# P_IN.net
KiCad netlist of a schematic drawn in Altium Designer
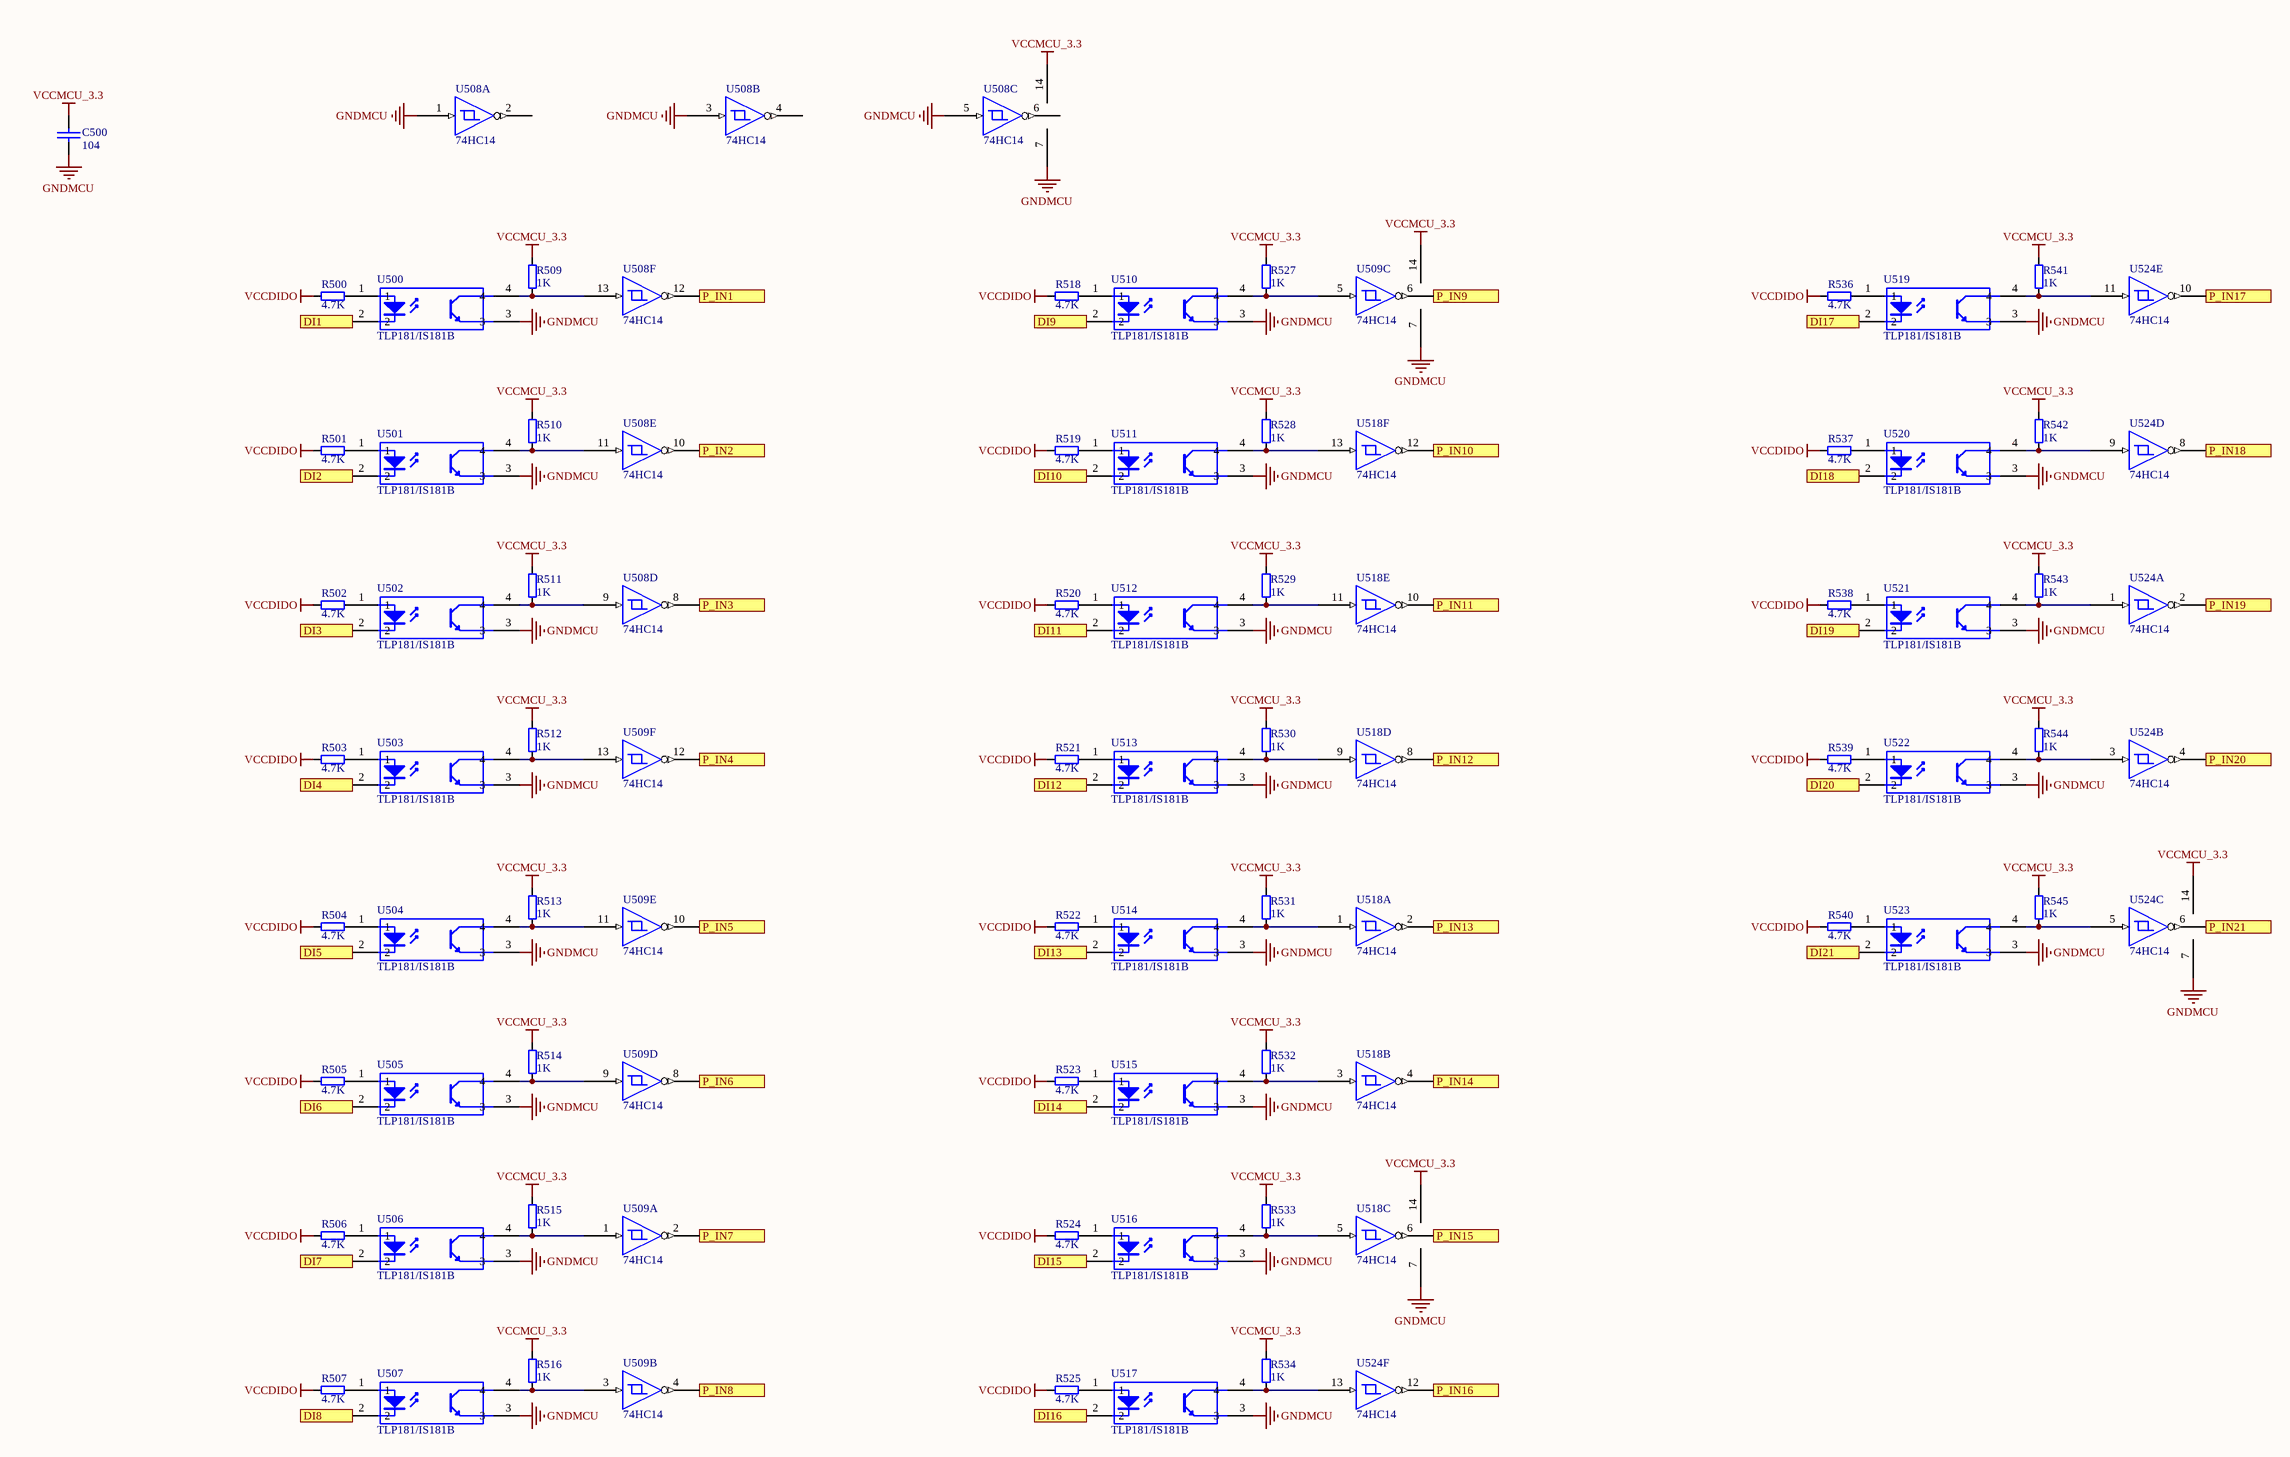
[diagram p0: P_IN.SchDoc]

(export (version "E")
  (design (tool "Eeschema 10.0.6"))
  (components
    (comp (ref "C500")
      (value "104")
      (footprint "CAPC_E0805_2012X70N")
      (description "Capacitor")
      (libsource (lib "YGInfoSCHLib") (part "CAP"))
    )
    (comp (ref "R500")
      (value "4.7K")
      (footprint "RESC_E0805_2012X50N")
      (description "General Resistor")
      (libsource (lib "Resistor") (part "Res"))
    )
    (comp (ref "R501")
      (value "4.7K")
      (footprint "RESC_E0805_2012X50N")
      (description "General Resistor")
      (libsource (lib "Resistor") (part "Res"))
    )
    (comp (ref "R502")
      (value "4.7K")
      (footprint "RESC_E0805_2012X50N")
      (description "General Resistor")
      (libsource (lib "Resistor") (part "Res"))
    )
    (comp (ref "R503")
      (value "4.7K")
      (footprint "RESC_E0805_2012X50N")
      (description "General Resistor")
      (libsource (lib "Resistor") (part "Res"))
    )
    (comp (ref "R504")
      (value "4.7K")
      (footprint "RESC_E0805_2012X50N")
      (description "General Resistor")
      (libsource (lib "Resistor") (part "Res"))
    )
    (comp (ref "R505")
      (value "4.7K")
      (footprint "RESC_E0805_2012X50N")
      (description "General Resistor")
      (libsource (lib "Resistor") (part "Res"))
    )
    (comp (ref "R506")
      (value "4.7K")
      (footprint "RESC_E0805_2012X50N")
      (description "General Resistor")
      (libsource (lib "Resistor") (part "Res"))
    )
    (comp (ref "R507")
      (value "4.7K")
      (footprint "RESC_E0805_2012X50N")
      (description "General Resistor")
      (libsource (lib "Resistor") (part "Res"))
    )
    (comp (ref "R509")
      (value "1K")
      (footprint "RESC_E0805_2012X50N")
      (description "General Resistor")
      (libsource (lib "") (part "Res_1"))
    )
    (comp (ref "R510")
      (value "1K")
      (footprint "RESC_E0805_2012X50N")
      (description "General Resistor")
      (libsource (lib "") (part "Res_1"))
    )
    (comp (ref "R511")
      (value "1K")
      (footprint "RESC_E0805_2012X50N")
      (description "General Resistor")
      (libsource (lib "") (part "Res_1"))
    )
    (comp (ref "R512")
      (value "1K")
      (footprint "RESC_E0805_2012X50N")
      (description "General Resistor")
      (libsource (lib "") (part "Res_1"))
    )
    (comp (ref "R513")
      (value "1K")
      (footprint "RESC_E0805_2012X50N")
      (description "General Resistor")
      (libsource (lib "") (part "Res_1"))
    )
    (comp (ref "R514")
      (value "1K")
      (footprint "RESC_E0805_2012X50N")
      (description "General Resistor")
      (libsource (lib "") (part "Res_1"))
    )
    (comp (ref "R515")
      (value "1K")
      (footprint "RESC_E0805_2012X50N")
      (description "General Resistor")
      (libsource (lib "") (part "Res_1"))
    )
    (comp (ref "R516")
      (value "1K")
      (footprint "RESC_E0805_2012X50N")
      (description "General Resistor")
      (libsource (lib "") (part "Res_1"))
    )
    (comp (ref "R518")
      (value "4.7K")
      (footprint "RESC_E0805_2012X50N")
      (description "General Resistor")
      (libsource (lib "Resistor") (part "Res"))
    )
    (comp (ref "R519")
      (value "4.7K")
      (footprint "RESC_E0805_2012X50N")
      (description "General Resistor")
      (libsource (lib "Resistor") (part "Res"))
    )
    (comp (ref "R520")
      (value "4.7K")
      (footprint "RESC_E0805_2012X50N")
      (description "General Resistor")
      (libsource (lib "Resistor") (part "Res"))
    )
    (comp (ref "R521")
      (value "4.7K")
      (footprint "RESC_E0805_2012X50N")
      (description "General Resistor")
      (libsource (lib "Resistor") (part "Res"))
    )
    (comp (ref "R522")
      (value "4.7K")
      (footprint "RESC_E0805_2012X50N")
      (description "General Resistor")
      (libsource (lib "Resistor") (part "Res"))
    )
    (comp (ref "R523")
      (value "4.7K")
      (footprint "RESC_E0805_2012X50N")
      (description "General Resistor")
      (libsource (lib "Resistor") (part "Res"))
    )
    (comp (ref "R524")
      (value "4.7K")
      (footprint "RESC_E0805_2012X50N")
      (description "General Resistor")
      (libsource (lib "Resistor") (part "Res"))
    )
    (comp (ref "R525")
      (value "4.7K")
      (footprint "RESC_E0805_2012X50N")
      (description "General Resistor")
      (libsource (lib "Resistor") (part "Res"))
    )
    (comp (ref "R527")
      (value "1K")
      (footprint "RESC_E0805_2012X50N")
      (description "General Resistor")
      (libsource (lib "") (part "Res_1"))
    )
    (comp (ref "R528")
      (value "1K")
      (footprint "RESC_E0805_2012X50N")
      (description "General Resistor")
      (libsource (lib "") (part "Res_1"))
    )
    (comp (ref "R529")
      (value "1K")
      (footprint "RESC_E0805_2012X50N")
      (description "General Resistor")
      (libsource (lib "") (part "Res_1"))
    )
    (comp (ref "R530")
      (value "1K")
      (footprint "RESC_E0805_2012X50N")
      (description "General Resistor")
      (libsource (lib "") (part "Res_1"))
    )
    (comp (ref "R531")
      (value "1K")
      (footprint "RESC_E0805_2012X50N")
      (description "General Resistor")
      (libsource (lib "") (part "Res_1"))
    )
    (comp (ref "R532")
      (value "1K")
      (footprint "RESC_E0805_2012X50N")
      (description "General Resistor")
      (libsource (lib "") (part "Res_1"))
    )
    (comp (ref "R533")
      (value "1K")
      (footprint "RESC_E0805_2012X50N")
      (description "General Resistor")
      (libsource (lib "") (part "Res_1"))
    )
    (comp (ref "R534")
      (value "1K")
      (footprint "RESC_E0805_2012X50N")
      (description "General Resistor")
      (libsource (lib "") (part "Res_1"))
    )
    (comp (ref "R536")
      (value "4.7K")
      (footprint "RESC_E0805_2012X50N")
      (description "General Resistor")
      (libsource (lib "Resistor") (part "Res"))
    )
    (comp (ref "R537")
      (value "4.7K")
      (footprint "RESC_E0805_2012X50N")
      (description "General Resistor")
      (libsource (lib "Resistor") (part "Res"))
    )
    (comp (ref "R538")
      (value "4.7K")
      (footprint "RESC_E0805_2012X50N")
      (description "General Resistor")
      (libsource (lib "Resistor") (part "Res"))
    )
    (comp (ref "R539")
      (value "4.7K")
      (footprint "RESC_E0805_2012X50N")
      (description "General Resistor")
      (libsource (lib "Resistor") (part "Res"))
    )
    (comp (ref "R540")
      (value "4.7K")
      (footprint "RESC_E0805_2012X50N")
      (description "General Resistor")
      (libsource (lib "Resistor") (part "Res"))
    )
    (comp (ref "R541")
      (value "1K")
      (footprint "RESC_E0805_2012X50N")
      (description "General Resistor")
      (libsource (lib "") (part "Res_1"))
    )
    (comp (ref "R542")
      (value "1K")
      (footprint "RESC_E0805_2012X50N")
      (description "General Resistor")
      (libsource (lib "") (part "Res_1"))
    )
    (comp (ref "R543")
      (value "1K")
      (footprint "RESC_E0805_2012X50N")
      (description "General Resistor")
      (libsource (lib "") (part "Res_1"))
    )
    (comp (ref "R544")
      (value "1K")
      (footprint "RESC_E0805_2012X50N")
      (description "General Resistor")
      (libsource (lib "") (part "Res_1"))
    )
    (comp (ref "R545")
      (value "1K")
      (footprint "RESC_E0805_2012X50N")
      (description "General Resistor")
      (libsource (lib "") (part "Res_1"))
    )
    (comp (ref "U500")
      (value "TLP181/IS181B")
      (footprint "TLP181")
      (description "光耦隔离")
      (libsource (lib "YGInfoSCHLib") (part "TLP181"))
    )
    (comp (ref "U501")
      (value "TLP181/IS181B")
      (footprint "TLP181")
      (description "光耦隔离")
      (libsource (lib "YGInfoSCHLib") (part "TLP181"))
    )
    (comp (ref "U502")
      (value "TLP181/IS181B")
      (footprint "TLP181")
      (description "光耦隔离")
      (libsource (lib "YGInfoSCHLib") (part "TLP181"))
    )
    (comp (ref "U503")
      (value "TLP181/IS181B")
      (footprint "TLP181")
      (description "光耦隔离")
      (libsource (lib "YGInfoSCHLib") (part "TLP181"))
    )
    (comp (ref "U504")
      (value "TLP181/IS181B")
      (footprint "TLP181")
      (description "光耦隔离")
      (libsource (lib "YGInfoSCHLib") (part "TLP181"))
    )
    (comp (ref "U505")
      (value "TLP181/IS181B")
      (footprint "TLP181")
      (description "光耦隔离")
      (libsource (lib "YGInfoSCHLib") (part "TLP181"))
    )
    (comp (ref "U506")
      (value "TLP181/IS181B")
      (footprint "TLP181")
      (description "光耦隔离")
      (libsource (lib "YGInfoSCHLib") (part "TLP181"))
    )
    (comp (ref "U507")
      (value "TLP181/IS181B")
      (footprint "TLP181")
      (description "光耦隔离")
      (libsource (lib "YGInfoSCHLib") (part "TLP181"))
    )
    (comp (ref "U508") (value "74HC14") (footprint "SO-14") (libsource (lib "YGInfoSCHLib") (part "74LS14")))
    (comp (ref "U509") (value "74HC14") (footprint "SO-14") (libsource (lib "YGInfoSCHLib") (part "74LS14")))
    (comp (ref "U510")
      (value "TLP181/IS181B")
      (footprint "TLP181")
      (description "光耦隔离")
      (libsource (lib "YGInfoSCHLib") (part "TLP181"))
    )
    (comp (ref "U511")
      (value "TLP181/IS181B")
      (footprint "TLP181")
      (description "光耦隔离")
      (libsource (lib "YGInfoSCHLib") (part "TLP181"))
    )
    (comp (ref "U512")
      (value "TLP181/IS181B")
      (footprint "TLP181")
      (description "光耦隔离")
      (libsource (lib "YGInfoSCHLib") (part "TLP181"))
    )
    (comp (ref "U513")
      (value "TLP181/IS181B")
      (footprint "TLP181")
      (description "光耦隔离")
      (libsource (lib "YGInfoSCHLib") (part "TLP181"))
    )
    (comp (ref "U514")
      (value "TLP181/IS181B")
      (footprint "TLP181")
      (description "光耦隔离")
      (libsource (lib "YGInfoSCHLib") (part "TLP181"))
    )
    (comp (ref "U515")
      (value "TLP181/IS181B")
      (footprint "TLP181")
      (description "光耦隔离")
      (libsource (lib "YGInfoSCHLib") (part "TLP181"))
    )
    (comp (ref "U516")
      (value "TLP181/IS181B")
      (footprint "TLP181")
      (description "光耦隔离")
      (libsource (lib "YGInfoSCHLib") (part "TLP181"))
    )
    (comp (ref "U517")
      (value "TLP181/IS181B")
      (footprint "TLP181")
      (description "光耦隔离")
      (libsource (lib "YGInfoSCHLib") (part "TLP181"))
    )
    (comp (ref "U518") (value "74HC14") (footprint "SO-14") (libsource (lib "") (part "74LS14_5")))
    (comp (ref "U519")
      (value "TLP181/IS181B")
      (footprint "TLP181")
      (description "光耦隔离")
      (libsource (lib "YGInfoSCHLib") (part "TLP181"))
    )
    (comp (ref "U520")
      (value "TLP181/IS181B")
      (footprint "TLP181")
      (description "光耦隔离")
      (libsource (lib "YGInfoSCHLib") (part "TLP181"))
    )
    (comp (ref "U521")
      (value "TLP181/IS181B")
      (footprint "TLP181")
      (description "光耦隔离")
      (libsource (lib "YGInfoSCHLib") (part "TLP181"))
    )
    (comp (ref "U522")
      (value "TLP181/IS181B")
      (footprint "TLP181")
      (description "光耦隔离")
      (libsource (lib "YGInfoSCHLib") (part "TLP181"))
    )
    (comp (ref "U523")
      (value "TLP181/IS181B")
      (footprint "TLP181")
      (description "光耦隔离")
      (libsource (lib "YGInfoSCHLib") (part "TLP181"))
    )
    (comp (ref "U524") (value "74HC14") (footprint "SO-14") (libsource (lib "") (part "74LS14_4")))
  )
  (nets
    (net (code "1") (name "/DI1") (class "Default")
      (node (ref "U500") (pin "2") (pinfunction "2_2") (pintype "passive"))
    )
    (net (code "2") (name "/DI2") (class "Default")
      (node (ref "U501") (pin "2") (pinfunction "2_2") (pintype "passive"))
    )
    (net (code "3") (name "/DI3") (class "Default")
      (node (ref "U502") (pin "2") (pinfunction "2_2") (pintype "passive"))
    )
    (net (code "4") (name "/DI4") (class "Default")
      (node (ref "U503") (pin "2") (pinfunction "2_2") (pintype "passive"))
    )
    (net (code "5") (name "/DI5") (class "Default")
      (node (ref "U504") (pin "2") (pinfunction "2_2") (pintype "passive"))
    )
    (net (code "6") (name "/DI6") (class "Default")
      (node (ref "U505") (pin "2") (pinfunction "2_2") (pintype "passive"))
    )
    (net (code "7") (name "/DI7") (class "Default")
      (node (ref "U506") (pin "2") (pinfunction "2_2") (pintype "passive"))
    )
    (net (code "8") (name "/DI8") (class "Default")
      (node (ref "U507") (pin "2") (pinfunction "2_2") (pintype "passive"))
    )
    (net (code "9") (name "/DI9") (class "Default")
      (node (ref "U510") (pin "2") (pinfunction "2_2") (pintype "passive"))
    )
    (net (code "10") (name "/DI10") (class "Default")
      (node (ref "U511") (pin "2") (pinfunction "2_2") (pintype "passive"))
    )
    (net (code "11") (name "/DI11") (class "Default")
      (node (ref "U512") (pin "2") (pinfunction "2_2") (pintype "passive"))
    )
    (net (code "12") (name "/DI12") (class "Default")
      (node (ref "U513") (pin "2") (pinfunction "2_2") (pintype "passive"))
    )
    (net (code "13") (name "/DI13") (class "Default")
      (node (ref "U514") (pin "2") (pinfunction "2_2") (pintype "passive"))
    )
    (net (code "14") (name "/DI14") (class "Default")
      (node (ref "U515") (pin "2") (pinfunction "2_2") (pintype "passive"))
    )
    (net (code "15") (name "/DI15") (class "Default")
      (node (ref "U516") (pin "2") (pinfunction "2_2") (pintype "passive"))
    )
    (net (code "16") (name "/DI16") (class "Default")
      (node (ref "U517") (pin "2") (pinfunction "2_2") (pintype "passive"))
    )
    (net (code "17") (name "/DI17") (class "Default")
      (node (ref "U519") (pin "2") (pinfunction "2_2") (pintype "passive"))
    )
    (net (code "18") (name "/DI18") (class "Default")
      (node (ref "U520") (pin "2") (pinfunction "2_2") (pintype "passive"))
    )
    (net (code "19") (name "/DI19") (class "Default")
      (node (ref "U521") (pin "2") (pinfunction "2_2") (pintype "passive"))
    )
    (net (code "20") (name "/DI20") (class "Default")
      (node (ref "U522") (pin "2") (pinfunction "2_2") (pintype "passive"))
    )
    (net (code "21") (name "/DI21") (class "Default")
      (node (ref "U523") (pin "2") (pinfunction "2_2") (pintype "passive"))
    )
    (net (code "22") (name "/P_IN1") (class "Default") (node (ref "U508") (pin "12") (pintype "output")))
    (net (code "23") (name "/P_IN2") (class "Default") (node (ref "U508") (pin "10") (pintype "output")))
    (net (code "24") (name "/P_IN3") (class "Default") (node (ref "U508") (pin "8") (pintype "output")))
    (net (code "25") (name "/P_IN4") (class "Default") (node (ref "U509") (pin "12") (pintype "output")))
    (net (code "26") (name "/P_IN5") (class "Default") (node (ref "U509") (pin "10") (pintype "output")))
    (net (code "27") (name "/P_IN6") (class "Default") (node (ref "U509") (pin "8") (pintype "output")))
    (net (code "28") (name "/P_IN7") (class "Default") (node (ref "U509") (pin "2") (pintype "output")))
    (net (code "29") (name "/P_IN8") (class "Default") (node (ref "U509") (pin "4") (pintype "output")))
    (net (code "30") (name "/P_IN9") (class "Default") (node (ref "U509") (pin "6") (pintype "output")))
    (net (code "31") (name "/P_IN10") (class "Default") (node (ref "U518") (pin "12") (pintype "output")))
    (net (code "32") (name "/P_IN11") (class "Default") (node (ref "U518") (pin "10") (pintype "output")))
    (net (code "33") (name "/P_IN12") (class "Default") (node (ref "U518") (pin "8") (pintype "output")))
    (net (code "34") (name "/P_IN13") (class "Default") (node (ref "U518") (pin "2") (pintype "output")))
    (net (code "35") (name "/P_IN14") (class "Default") (node (ref "U518") (pin "4") (pintype "output")))
    (net (code "36") (name "/P_IN15") (class "Default") (node (ref "U518") (pin "6") (pintype "output")))
    (net (code "37") (name "/P_IN16") (class "Default") (node (ref "U524") (pin "12") (pintype "output")))
    (net (code "38") (name "/P_IN17") (class "Default") (node (ref "U524") (pin "10") (pintype "output")))
    (net (code "39") (name "/P_IN18") (class "Default") (node (ref "U524") (pin "8") (pintype "output")))
    (net (code "40") (name "/P_IN19") (class "Default") (node (ref "U524") (pin "2") (pintype "output")))
    (net (code "41") (name "/P_IN20") (class "Default") (node (ref "U524") (pin "4") (pintype "output")))
    (net (code "42") (name "/P_IN21") (class "Default") (node (ref "U524") (pin "6") (pintype "output")))
    (net (code "43") (name "GNDMCU") (class "Default")
      (node (ref "C500") (pin "2") (pinfunction "2_2") (pintype "passive"))
      (node (ref "U500") (pin "3") (pinfunction "3_3") (pintype "passive"))
      (node (ref "U501") (pin "3") (pinfunction "3_3") (pintype "passive"))
      (node (ref "U502") (pin "3") (pinfunction "3_3") (pintype "passive"))
      (node (ref "U503") (pin "3") (pinfunction "3_3") (pintype "passive"))
      (node (ref "U504") (pin "3") (pinfunction "3_3") (pintype "passive"))
      (node (ref "U505") (pin "3") (pinfunction "3_3") (pintype "passive"))
      (node (ref "U506") (pin "3") (pinfunction "3_3") (pintype "passive"))
      (node (ref "U507") (pin "3") (pinfunction "3_3") (pintype "passive"))
      (node (ref "U508") (pin "1") (pintype "input"))
      (node (ref "U508") (pin "3") (pintype "input"))
      (node (ref "U508") (pin "5") (pintype "input"))
      (node (ref "U508") (pin "7") (pintype "power_in"))
      (node (ref "U509") (pin "7") (pintype "power_in"))
      (node (ref "U510") (pin "3") (pinfunction "3_3") (pintype "passive"))
      (node (ref "U511") (pin "3") (pinfunction "3_3") (pintype "passive"))
      (node (ref "U512") (pin "3") (pinfunction "3_3") (pintype "passive"))
      (node (ref "U513") (pin "3") (pinfunction "3_3") (pintype "passive"))
      (node (ref "U514") (pin "3") (pinfunction "3_3") (pintype "passive"))
      (node (ref "U515") (pin "3") (pinfunction "3_3") (pintype "passive"))
      (node (ref "U516") (pin "3") (pinfunction "3_3") (pintype "passive"))
      (node (ref "U517") (pin "3") (pinfunction "3_3") (pintype "passive"))
      (node (ref "U518") (pin "7") (pintype "power_in"))
      (node (ref "U519") (pin "3") (pinfunction "3_3") (pintype "passive"))
      (node (ref "U520") (pin "3") (pinfunction "3_3") (pintype "passive"))
      (node (ref "U521") (pin "3") (pinfunction "3_3") (pintype "passive"))
      (node (ref "U522") (pin "3") (pinfunction "3_3") (pintype "passive"))
      (node (ref "U523") (pin "3") (pinfunction "3_3") (pintype "passive"))
      (node (ref "U524") (pin "7") (pintype "power_in"))
    )
    (net (code "44") (name "Net-(R500-Pad1)") (class "Default")
      (node (ref "R500") (pin "1") (pinfunction "1_1") (pintype "passive"))
      (node (ref "U500") (pin "1") (pinfunction "1_1") (pintype "passive"))
    )
    (net (code "45") (name "Net-(R501-Pad1)") (class "Default")
      (node (ref "R501") (pin "1") (pinfunction "1_1") (pintype "passive"))
      (node (ref "U501") (pin "1") (pinfunction "1_1") (pintype "passive"))
    )
    (net (code "46") (name "Net-(R502-Pad1)") (class "Default")
      (node (ref "R502") (pin "1") (pinfunction "1_1") (pintype "passive"))
      (node (ref "U502") (pin "1") (pinfunction "1_1") (pintype "passive"))
    )
    (net (code "47") (name "Net-(R503-Pad1)") (class "Default")
      (node (ref "R503") (pin "1") (pinfunction "1_1") (pintype "passive"))
      (node (ref "U503") (pin "1") (pinfunction "1_1") (pintype "passive"))
    )
    (net (code "48") (name "Net-(R504-Pad1)") (class "Default")
      (node (ref "R504") (pin "1") (pinfunction "1_1") (pintype "passive"))
      (node (ref "U504") (pin "1") (pinfunction "1_1") (pintype "passive"))
    )
    (net (code "49") (name "Net-(R505-Pad1)") (class "Default")
      (node (ref "R505") (pin "1") (pinfunction "1_1") (pintype "passive"))
      (node (ref "U505") (pin "1") (pinfunction "1_1") (pintype "passive"))
    )
    (net (code "50") (name "Net-(R506-Pad1)") (class "Default")
      (node (ref "R506") (pin "1") (pinfunction "1_1") (pintype "passive"))
      (node (ref "U506") (pin "1") (pinfunction "1_1") (pintype "passive"))
    )
    (net (code "51") (name "Net-(R507-Pad1)") (class "Default")
      (node (ref "R507") (pin "1") (pinfunction "1_1") (pintype "passive"))
      (node (ref "U507") (pin "1") (pinfunction "1_1") (pintype "passive"))
    )
    (net (code "52") (name "Net-(R509-Pad1)") (class "Default")
      (node (ref "R509") (pin "1") (pinfunction "1_1") (pintype "passive"))
      (node (ref "U500") (pin "4") (pinfunction "4_4") (pintype "passive"))
      (node (ref "U508") (pin "13") (pintype "input"))
    )
    (net (code "53") (name "Net-(R510-Pad1)") (class "Default")
      (node (ref "R510") (pin "1") (pinfunction "1_1") (pintype "passive"))
      (node (ref "U501") (pin "4") (pinfunction "4_4") (pintype "passive"))
      (node (ref "U508") (pin "11") (pintype "input"))
    )
    (net (code "54") (name "Net-(R511-Pad1)") (class "Default")
      (node (ref "R511") (pin "1") (pinfunction "1_1") (pintype "passive"))
      (node (ref "U502") (pin "4") (pinfunction "4_4") (pintype "passive"))
      (node (ref "U508") (pin "9") (pintype "input"))
    )
    (net (code "55") (name "Net-(R512-Pad1)") (class "Default")
      (node (ref "R512") (pin "1") (pinfunction "1_1") (pintype "passive"))
      (node (ref "U503") (pin "4") (pinfunction "4_4") (pintype "passive"))
      (node (ref "U509") (pin "13") (pintype "input"))
    )
    (net (code "56") (name "Net-(R513-Pad1)") (class "Default")
      (node (ref "R513") (pin "1") (pinfunction "1_1") (pintype "passive"))
      (node (ref "U504") (pin "4") (pinfunction "4_4") (pintype "passive"))
      (node (ref "U509") (pin "11") (pintype "input"))
    )
    (net (code "57") (name "Net-(R514-Pad1)") (class "Default")
      (node (ref "R514") (pin "1") (pinfunction "1_1") (pintype "passive"))
      (node (ref "U505") (pin "4") (pinfunction "4_4") (pintype "passive"))
      (node (ref "U509") (pin "9") (pintype "input"))
    )
    (net (code "58") (name "Net-(R515-Pad1)") (class "Default")
      (node (ref "R515") (pin "1") (pinfunction "1_1") (pintype "passive"))
      (node (ref "U506") (pin "4") (pinfunction "4_4") (pintype "passive"))
      (node (ref "U509") (pin "1") (pintype "input"))
    )
    (net (code "59") (name "Net-(R516-Pad1)") (class "Default")
      (node (ref "R516") (pin "1") (pinfunction "1_1") (pintype "passive"))
      (node (ref "U507") (pin "4") (pinfunction "4_4") (pintype "passive"))
      (node (ref "U509") (pin "3") (pintype "input"))
    )
    (net (code "60") (name "Net-(R518-Pad1)") (class "Default")
      (node (ref "R518") (pin "1") (pinfunction "1_1") (pintype "passive"))
      (node (ref "U510") (pin "1") (pinfunction "1_1") (pintype "passive"))
    )
    (net (code "61") (name "Net-(R519-Pad1)") (class "Default")
      (node (ref "R519") (pin "1") (pinfunction "1_1") (pintype "passive"))
      (node (ref "U511") (pin "1") (pinfunction "1_1") (pintype "passive"))
    )
    (net (code "62") (name "Net-(R520-Pad1)") (class "Default")
      (node (ref "R520") (pin "1") (pinfunction "1_1") (pintype "passive"))
      (node (ref "U512") (pin "1") (pinfunction "1_1") (pintype "passive"))
    )
    (net (code "63") (name "Net-(R521-Pad1)") (class "Default")
      (node (ref "R521") (pin "1") (pinfunction "1_1") (pintype "passive"))
      (node (ref "U513") (pin "1") (pinfunction "1_1") (pintype "passive"))
    )
    (net (code "64") (name "Net-(R522-Pad1)") (class "Default")
      (node (ref "R522") (pin "1") (pinfunction "1_1") (pintype "passive"))
      (node (ref "U514") (pin "1") (pinfunction "1_1") (pintype "passive"))
    )
    (net (code "65") (name "Net-(R523-Pad1)") (class "Default")
      (node (ref "R523") (pin "1") (pinfunction "1_1") (pintype "passive"))
      (node (ref "U515") (pin "1") (pinfunction "1_1") (pintype "passive"))
    )
    (net (code "66") (name "Net-(R524-Pad1)") (class "Default")
      (node (ref "R524") (pin "1") (pinfunction "1_1") (pintype "passive"))
      (node (ref "U516") (pin "1") (pinfunction "1_1") (pintype "passive"))
    )
    (net (code "67") (name "Net-(R525-Pad1)") (class "Default")
      (node (ref "R525") (pin "1") (pinfunction "1_1") (pintype "passive"))
      (node (ref "U517") (pin "1") (pinfunction "1_1") (pintype "passive"))
    )
    (net (code "68") (name "Net-(R527-Pad1)") (class "Default")
      (node (ref "R527") (pin "1") (pinfunction "1_1") (pintype "passive"))
      (node (ref "U509") (pin "5") (pintype "input"))
      (node (ref "U510") (pin "4") (pinfunction "4_4") (pintype "passive"))
    )
    (net (code "69") (name "Net-(R528-Pad1)") (class "Default")
      (node (ref "R528") (pin "1") (pinfunction "1_1") (pintype "passive"))
      (node (ref "U511") (pin "4") (pinfunction "4_4") (pintype "passive"))
      (node (ref "U518") (pin "13") (pintype "input"))
    )
    (net (code "70") (name "Net-(R529-Pad1)") (class "Default")
      (node (ref "R529") (pin "1") (pinfunction "1_1") (pintype "passive"))
      (node (ref "U512") (pin "4") (pinfunction "4_4") (pintype "passive"))
      (node (ref "U518") (pin "11") (pintype "input"))
    )
    (net (code "71") (name "Net-(R530-Pad1)") (class "Default")
      (node (ref "R530") (pin "1") (pinfunction "1_1") (pintype "passive"))
      (node (ref "U513") (pin "4") (pinfunction "4_4") (pintype "passive"))
      (node (ref "U518") (pin "9") (pintype "input"))
    )
    (net (code "72") (name "Net-(R531-Pad1)") (class "Default")
      (node (ref "R531") (pin "1") (pinfunction "1_1") (pintype "passive"))
      (node (ref "U514") (pin "4") (pinfunction "4_4") (pintype "passive"))
      (node (ref "U518") (pin "1") (pintype "input"))
    )
    (net (code "73") (name "Net-(R532-Pad1)") (class "Default")
      (node (ref "R532") (pin "1") (pinfunction "1_1") (pintype "passive"))
      (node (ref "U515") (pin "4") (pinfunction "4_4") (pintype "passive"))
      (node (ref "U518") (pin "3") (pintype "input"))
    )
    (net (code "74") (name "Net-(R533-Pad1)") (class "Default")
      (node (ref "R533") (pin "1") (pinfunction "1_1") (pintype "passive"))
      (node (ref "U516") (pin "4") (pinfunction "4_4") (pintype "passive"))
      (node (ref "U518") (pin "5") (pintype "input"))
    )
    (net (code "75") (name "Net-(R534-Pad1)") (class "Default")
      (node (ref "R534") (pin "1") (pinfunction "1_1") (pintype "passive"))
      (node (ref "U517") (pin "4") (pinfunction "4_4") (pintype "passive"))
      (node (ref "U524") (pin "13") (pintype "input"))
    )
    (net (code "76") (name "Net-(R536-Pad1)") (class "Default")
      (node (ref "R536") (pin "1") (pinfunction "1_1") (pintype "passive"))
      (node (ref "U519") (pin "1") (pinfunction "1_1") (pintype "passive"))
    )
    (net (code "77") (name "Net-(R537-Pad1)") (class "Default")
      (node (ref "R537") (pin "1") (pinfunction "1_1") (pintype "passive"))
      (node (ref "U520") (pin "1") (pinfunction "1_1") (pintype "passive"))
    )
    (net (code "78") (name "Net-(R538-Pad1)") (class "Default")
      (node (ref "R538") (pin "1") (pinfunction "1_1") (pintype "passive"))
      (node (ref "U521") (pin "1") (pinfunction "1_1") (pintype "passive"))
    )
    (net (code "79") (name "Net-(R539-Pad1)") (class "Default")
      (node (ref "R539") (pin "1") (pinfunction "1_1") (pintype "passive"))
      (node (ref "U522") (pin "1") (pinfunction "1_1") (pintype "passive"))
    )
    (net (code "80") (name "Net-(R540-Pad1)") (class "Default")
      (node (ref "R540") (pin "1") (pinfunction "1_1") (pintype "passive"))
      (node (ref "U523") (pin "1") (pinfunction "1_1") (pintype "passive"))
    )
    (net (code "81") (name "Net-(R541-Pad1)") (class "Default")
      (node (ref "R541") (pin "1") (pinfunction "1_1") (pintype "passive"))
      (node (ref "U519") (pin "4") (pinfunction "4_4") (pintype "passive"))
      (node (ref "U524") (pin "11") (pintype "input"))
    )
    (net (code "82") (name "Net-(R542-Pad1)") (class "Default")
      (node (ref "R542") (pin "1") (pinfunction "1_1") (pintype "passive"))
      (node (ref "U520") (pin "4") (pinfunction "4_4") (pintype "passive"))
      (node (ref "U524") (pin "9") (pintype "input"))
    )
    (net (code "83") (name "Net-(R543-Pad1)") (class "Default")
      (node (ref "R543") (pin "1") (pinfunction "1_1") (pintype "passive"))
      (node (ref "U521") (pin "4") (pinfunction "4_4") (pintype "passive"))
      (node (ref "U524") (pin "1") (pintype "input"))
    )
    (net (code "84") (name "Net-(R544-Pad1)") (class "Default")
      (node (ref "R544") (pin "1") (pinfunction "1_1") (pintype "passive"))
      (node (ref "U522") (pin "4") (pinfunction "4_4") (pintype "passive"))
      (node (ref "U524") (pin "3") (pintype "input"))
    )
    (net (code "85") (name "Net-(R545-Pad1)") (class "Default")
      (node (ref "R545") (pin "1") (pinfunction "1_1") (pintype "passive"))
      (node (ref "U523") (pin "4") (pinfunction "4_4") (pintype "passive"))
      (node (ref "U524") (pin "5") (pintype "input"))
    )
    (net (code "86") (name "VCCDIDO") (class "Default")
      (node (ref "R500") (pin "2") (pinfunction "2_2") (pintype "passive"))
      (node (ref "R501") (pin "2") (pinfunction "2_2") (pintype "passive"))
      (node (ref "R502") (pin "2") (pinfunction "2_2") (pintype "passive"))
      (node (ref "R503") (pin "2") (pinfunction "2_2") (pintype "passive"))
      (node (ref "R504") (pin "2") (pinfunction "2_2") (pintype "passive"))
      (node (ref "R505") (pin "2") (pinfunction "2_2") (pintype "passive"))
      (node (ref "R506") (pin "2") (pinfunction "2_2") (pintype "passive"))
      (node (ref "R507") (pin "2") (pinfunction "2_2") (pintype "passive"))
      (node (ref "R518") (pin "2") (pinfunction "2_2") (pintype "passive"))
      (node (ref "R519") (pin "2") (pinfunction "2_2") (pintype "passive"))
      (node (ref "R520") (pin "2") (pinfunction "2_2") (pintype "passive"))
      (node (ref "R521") (pin "2") (pinfunction "2_2") (pintype "passive"))
      (node (ref "R522") (pin "2") (pinfunction "2_2") (pintype "passive"))
      (node (ref "R523") (pin "2") (pinfunction "2_2") (pintype "passive"))
      (node (ref "R524") (pin "2") (pinfunction "2_2") (pintype "passive"))
      (node (ref "R525") (pin "2") (pinfunction "2_2") (pintype "passive"))
      (node (ref "R536") (pin "2") (pinfunction "2_2") (pintype "passive"))
      (node (ref "R537") (pin "2") (pinfunction "2_2") (pintype "passive"))
      (node (ref "R538") (pin "2") (pinfunction "2_2") (pintype "passive"))
      (node (ref "R539") (pin "2") (pinfunction "2_2") (pintype "passive"))
      (node (ref "R540") (pin "2") (pinfunction "2_2") (pintype "passive"))
    )
    (net (code "87") (name "VCCMCU_3.3") (class "Default")
      (node (ref "C500") (pin "1") (pinfunction "1_1") (pintype "passive"))
      (node (ref "R509") (pin "2") (pinfunction "2_2") (pintype "passive"))
      (node (ref "R510") (pin "2") (pinfunction "2_2") (pintype "passive"))
      (node (ref "R511") (pin "2") (pinfunction "2_2") (pintype "passive"))
      (node (ref "R512") (pin "2") (pinfunction "2_2") (pintype "passive"))
      (node (ref "R513") (pin "2") (pinfunction "2_2") (pintype "passive"))
      (node (ref "R514") (pin "2") (pinfunction "2_2") (pintype "passive"))
      (node (ref "R515") (pin "2") (pinfunction "2_2") (pintype "passive"))
      (node (ref "R516") (pin "2") (pinfunction "2_2") (pintype "passive"))
      (node (ref "R527") (pin "2") (pinfunction "2_2") (pintype "passive"))
      (node (ref "R528") (pin "2") (pinfunction "2_2") (pintype "passive"))
      (node (ref "R529") (pin "2") (pinfunction "2_2") (pintype "passive"))
      (node (ref "R530") (pin "2") (pinfunction "2_2") (pintype "passive"))
      (node (ref "R531") (pin "2") (pinfunction "2_2") (pintype "passive"))
      (node (ref "R532") (pin "2") (pinfunction "2_2") (pintype "passive"))
      (node (ref "R533") (pin "2") (pinfunction "2_2") (pintype "passive"))
      (node (ref "R534") (pin "2") (pinfunction "2_2") (pintype "passive"))
      (node (ref "R541") (pin "2") (pinfunction "2_2") (pintype "passive"))
      (node (ref "R542") (pin "2") (pinfunction "2_2") (pintype "passive"))
      (node (ref "R543") (pin "2") (pinfunction "2_2") (pintype "passive"))
      (node (ref "R544") (pin "2") (pinfunction "2_2") (pintype "passive"))
      (node (ref "R545") (pin "2") (pinfunction "2_2") (pintype "passive"))
      (node (ref "U508") (pin "14") (pintype "power_in"))
      (node (ref "U509") (pin "14") (pintype "power_in"))
      (node (ref "U518") (pin "14") (pintype "power_in"))
      (node (ref "U524") (pin "14") (pintype "power_in"))
    )
    (net (code "88") (name "unconnected-(U508-Pad2)") (class "Default")
      (node (ref "U508") (pin "2") (pintype "output"))
    )
    (net (code "89") (name "unconnected-(U508-Pad4)") (class "Default")
      (node (ref "U508") (pin "4") (pintype "output"))
    )
    (net (code "90") (name "unconnected-(U508-Pad6)") (class "Default")
      (node (ref "U508") (pin "6") (pintype "output"))
    )
  )
)
